# VU_meter_schematic.net
KiCad netlist of a schematic drawn in EAGLE
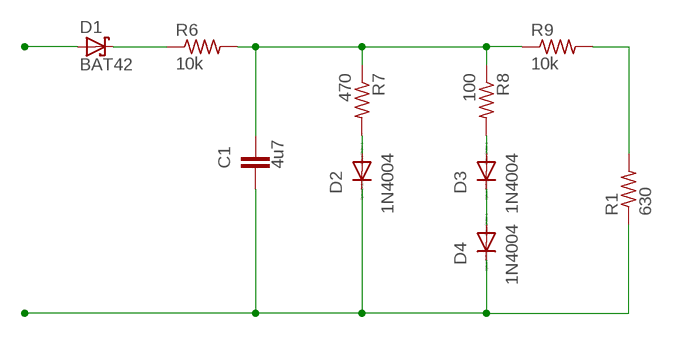
[diagram p0: schematic, sheet 1]

(export (version "E")
  (design (tool "Eeschema 10.0.6"))
  (components
    (comp (ref "C1")
      (value "4u7")
      (footprint "eagle-import:C2.5-3")
      (libsource (lib "eagle-import") (part "C2,5-3"))
    )
    (comp (ref "D1")
      (value "BAT42")
      (footprint "eagle-import:DO35-10")
      (libsource (lib "eagle-import") (part "BAT42"))
    )
    (comp (ref "D2")
      (value "1N4004")
      (footprint "eagle-import:DO41-10")
      (libsource (lib "eagle-import") (part "1N4004"))
    )
    (comp (ref "D3")
      (value "1N4004")
      (footprint "eagle-import:DO41-10")
      (libsource (lib "eagle-import") (part "1N4004"))
    )
    (comp (ref "D4")
      (value "1N4004")
      (footprint "eagle-import:DO41-10")
      (libsource (lib "eagle-import") (part "1N4004"))
    )
    (comp (ref "R1")
      (value "630")
      (footprint "eagle-import:0207_10")
      (libsource (lib "eagle-import") (part "R-US_0207/10"))
    )
    (comp (ref "R6")
      (value "10k")
      (footprint "eagle-import:0207_10")
      (libsource (lib "eagle-import") (part "R-US_0207/10"))
    )
    (comp (ref "R7")
      (value "470")
      (footprint "eagle-import:0207_10")
      (libsource (lib "eagle-import") (part "R-US_0207/10"))
    )
    (comp (ref "R8")
      (value "100")
      (footprint "eagle-import:0207_10")
      (libsource (lib "eagle-import") (part "R-US_0207/10"))
    )
    (comp (ref "R9")
      (value "10k")
      (footprint "eagle-import:0207_10")
      (libsource (lib "eagle-import") (part "R-US_0207/10"))
    )
  )
  (nets
    (net (code "1") (name "Net-(C1-Pad1)") (class "Default")
      (node (ref "C1") (pin "1") (pinfunction "1_1") (pintype "passive"))
      (node (ref "R6") (pin "2") (pinfunction "2_2") (pintype "passive"))
      (node (ref "R7") (pin "1") (pinfunction "1_1") (pintype "passive"))
      (node (ref "R8") (pin "1") (pinfunction "1_1") (pintype "passive"))
      (node (ref "R9") (pin "1") (pinfunction "1_1") (pintype "passive"))
    )
    (net (code "2") (name "Net-(C1-Pad2)") (class "Default")
      (node (ref "C1") (pin "2") (pinfunction "2_2") (pintype "passive"))
      (node (ref "D2") (pin "C") (pinfunction "C_C") (pintype "passive"))
      (node (ref "D4") (pin "C") (pinfunction "C_C") (pintype "passive"))
      (node (ref "R1") (pin "1") (pinfunction "1_1") (pintype "passive"))
    )
    (net (code "3") (name "Net-(D1-PadC)") (class "Default")
      (node (ref "D1") (pin "C") (pinfunction "C_C") (pintype "passive"))
      (node (ref "R6") (pin "1") (pinfunction "1_1") (pintype "passive"))
    )
    (net (code "4") (name "Net-(D2-PadA)") (class "Default")
      (node (ref "D2") (pin "A") (pinfunction "A_A") (pintype "passive"))
      (node (ref "R7") (pin "2") (pinfunction "2_2") (pintype "passive"))
    )
    (net (code "5") (name "Net-(D3-PadA)") (class "Default")
      (node (ref "D3") (pin "A") (pinfunction "A_A") (pintype "passive"))
      (node (ref "R8") (pin "2") (pinfunction "2_2") (pintype "passive"))
    )
    (net (code "6") (name "Net-(D3-PadC)") (class "Default")
      (node (ref "D3") (pin "C") (pinfunction "C_C") (pintype "passive"))
      (node (ref "D4") (pin "A") (pinfunction "A_A") (pintype "passive"))
    )
    (net (code "7") (name "Net-(R1-Pad2)") (class "Default")
      (node (ref "R1") (pin "2") (pinfunction "2_2") (pintype "passive"))
      (node (ref "R9") (pin "2") (pinfunction "2_2") (pintype "passive"))
    )
    (net (code "8") (name "unconnected-(D1-PadA)") (class "Default")
      (node (ref "D1") (pin "A") (pinfunction "A_A") (pintype "passive"))
    )
  )
)
